# RF_Transceiver_Sch.net
KiCad netlist of a schematic drawn in Altium Designer
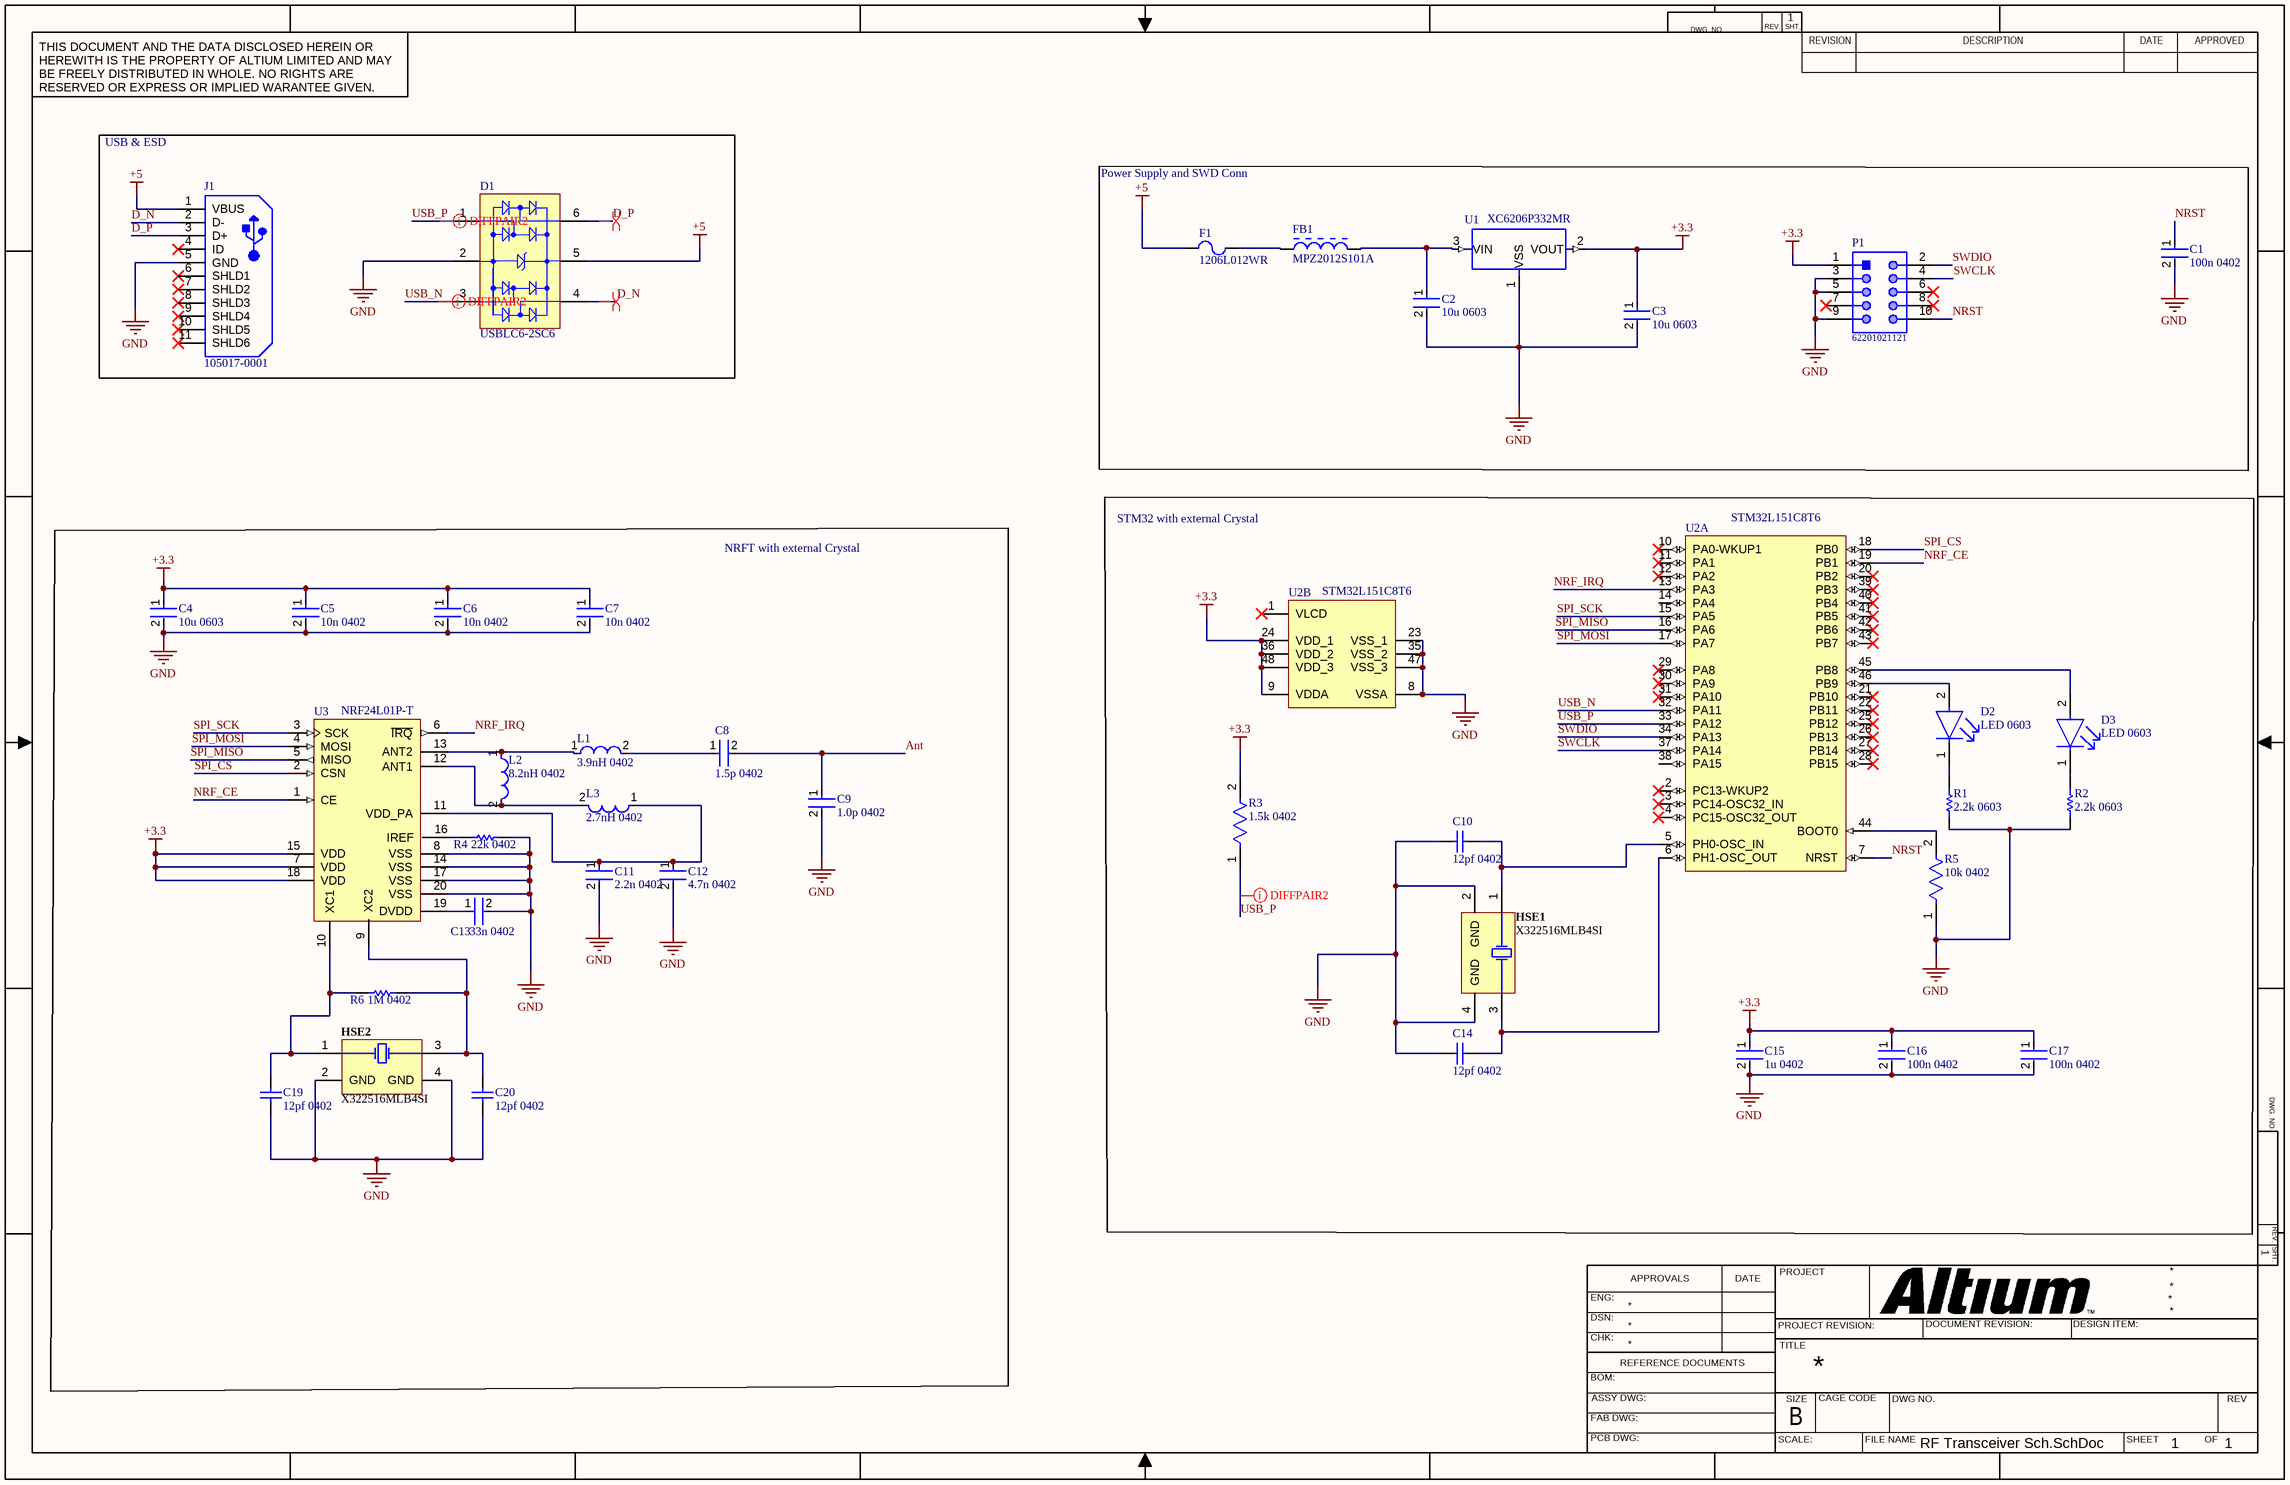
[diagram p0: RF Transceiver Sch.SchDoc]

(export (version "E")
  (design (tool "Eeschema 10.0.6"))
  (components
    (comp (ref "C1")
      (value "100n 0402")
      (footprint "FP-C0402-BB-MFG")
      (description "CAP CER 0.1UF 10V X5R 0402")
      (fields (field (name "MANUFACTURER") "Kemet") (field (name "TOLERANCE") "0.1"))
      (libsource (lib "Altium Content Vault") (part "b4654b650e69147ec39a6b967a45e02"))
    )
    (comp (ref "C2")
      (value "10u 0603")
      (footprint "FP-GRM188-0_1-e0_2_0_55-IPC_A")
      (description "Chip Multilayer Ceramic Capacitors for General Purpose, 0603, 10uF, X5R, 15%, 20%, 6.3V")
      (fields (field (name "VOLTAGE") "6.3V") (field (name "TOLERANCE") "20%"))
      (libsource (lib "Altium Content Vault") (part "02cd4be3c70576c341d710602a673aa"))
    )
    (comp (ref "C3")
      (value "10u 0603")
      (footprint "FP-GRM188-0_1-e0_2_0_55-IPC_A")
      (description "Chip Multilayer Ceramic Capacitors for General Purpose, 0603, 10uF, X5R, 15%, 20%, 6.3V")
      (fields (field (name "VOLTAGE") "6.3V") (field (name "TOLERANCE") "20%"))
      (libsource (lib "Altium Content Vault") (part "02cd4be3c70576c341d710602a673aa"))
    )
    (comp (ref "C4")
      (value "10u 0603")
      (footprint "FP-GRM188-0_1-e0_2_0_55-IPC_A")
      (description "Chip Multilayer Ceramic Capacitors for General Purpose, 0603, 10uF, X5R, 15%, 20%, 6.3V")
      (fields (field (name "VOLTAGE") "6.3V") (field (name "TOLERANCE") "20%"))
      (libsource (lib "Altium Content Vault") (part "02cd4be3c70576c341d710602a673aa"))
    )
    (comp (ref "C5")
      (value "10n 0402")
      (footprint "FP-C0402-BB-MFG")
      (description "CAP CER 0.1UF 10V X5R 0402")
      (fields (field (name "MANUFACTURER") "Kemet") (field (name "TOLERANCE") "0.1"))
      (libsource (lib "Altium Content Vault") (part "b4654b650e69147ec39a6b967a45e02"))
    )
    (comp (ref "C6")
      (value "10n 0402")
      (footprint "FP-C0402-BB-MFG")
      (description "CAP CER 0.1UF 10V X5R 0402")
      (fields (field (name "MANUFACTURER") "Kemet") (field (name "TOLERANCE") "0.1"))
      (libsource (lib "Altium Content Vault") (part "b4654b650e69147ec39a6b967a45e02"))
    )
    (comp (ref "C7")
      (value "10n 0402")
      (footprint "FP-C0402-BB-MFG")
      (description "CAP CER 0.1UF 10V X5R 0402")
      (fields (field (name "MANUFACTURER") "Kemet") (field (name "TOLERANCE") "0.1"))
      (libsource (lib "Altium Content Vault") (part "b4654b650e69147ec39a6b967a45e02"))
    )
    (comp (ref "C8")
      (value "1.5p 0402")
      (footprint "FP-C0402-BB-MFG")
      (description "CAP CER 0.1UF 10V X5R 0402")
      (fields (field (name "MANUFACTURER") "Kemet") (field (name "TOLERANCE") "0.1"))
      (libsource (lib "Altium Content Vault") (part "b4654b650e69147ec39a6b967a45e02"))
    )
    (comp (ref "C9")
      (value "1.0p 0402")
      (footprint "FP-C0402-BB-MFG")
      (description "CAP CER 0.1UF 10V X5R 0402")
      (fields (field (name "MANUFACTURER") "Kemet") (field (name "TOLERANCE") "0.1"))
      (libsource (lib "Altium Content Vault") (part "b4654b650e69147ec39a6b967a45e02"))
    )
    (comp (ref "C10")
      (value "12pf 0402")
      (footprint "CAPC1005X55X25ML05T10")
      (fields (field (name "PART NUMBER") "GRM1555C1H120GA01D") (field (name "MANUFACTURER") "Murata"))
      (libsource (lib "Altium Content Vault") (part "CAP"))
    )
    (comp (ref "C11")
      (value "2.2n 0402")
      (footprint "FP-C0402-BB-MFG")
      (description "CAP CER 0.1UF 10V X5R 0402")
      (fields (field (name "MANUFACTURER") "Kemet") (field (name "TOLERANCE") "0.1"))
      (libsource (lib "Altium Content Vault") (part "b4654b650e69147ec39a6b967a45e02"))
    )
    (comp (ref "C12")
      (value "4.7n 0402")
      (footprint "FP-C0402-BB-MFG")
      (description "CAP CER 0.1UF 10V X5R 0402")
      (fields (field (name "MANUFACTURER") "Kemet") (field (name "TOLERANCE") "0.1"))
      (libsource (lib "Altium Content Vault") (part "b4654b650e69147ec39a6b967a45e02"))
    )
    (comp (ref "C13")
      (value "33n 0402")
      (footprint "FP-C0402-BB-MFG")
      (description "CAP CER 0.1UF 10V X5R 0402")
      (fields (field (name "MANUFACTURER") "Kemet") (field (name "TOLERANCE") "0.1"))
      (libsource (lib "Altium Content Vault") (part "b4654b650e69147ec39a6b967a45e02"))
    )
    (comp (ref "C14")
      (value "12pf 0402")
      (footprint "CAPC1005X55X25ML05T10")
      (fields (field (name "PART NUMBER") "GRM1555C1H120GA01D") (field (name "MANUFACTURER") "Murata"))
      (libsource (lib "Altium Content Vault") (part "CAP"))
    )
    (comp (ref "C15")
      (value "1u 0402")
      (footprint "FP-GRM15-0_1-MFG")
      (description "CAP CER 1UF 10V X5R 0402")
      (fields
        (field (name "OCTOPART") "https://octopart.com/grm155r61a105ke15d-murata-197442")
        (field (name "MANUFACTURER PART NUMBER") "GRM155R61A105KE15D")
      )
      (libsource (lib "Altium Content Vault") (part "02cd4be3c70576c341d710602a673aa"))
    )
    (comp (ref "C16")
      (value "100n 0402")
      (footprint "FP-C0402-BB-MFG")
      (description "CAP CER 0.1UF 10V X5R 0402")
      (fields (field (name "MANUFACTURER") "Kemet") (field (name "TOLERANCE") "0.1"))
      (libsource (lib "Altium Content Vault") (part "b4654b650e69147ec39a6b967a45e02"))
    )
    (comp (ref "C17")
      (value "100n 0402")
      (footprint "FP-C0402-BB-MFG")
      (description "CAP CER 0.1UF 10V X5R 0402")
      (fields (field (name "MANUFACTURER") "Kemet") (field (name "TOLERANCE") "0.1"))
      (libsource (lib "Altium Content Vault") (part "b4654b650e69147ec39a6b967a45e02"))
    )
    (comp (ref "C19")
      (value "12pf 0402")
      (footprint "CAPC1005X55X25ML05T10")
      (fields (field (name "PART NUMBER") "GRM1555C1H120GA01D") (field (name "MANUFACTURER") "Murata"))
      (libsource (lib "Altium Content Vault") (part "CAP"))
    )
    (comp (ref "C20")
      (value "12pf 0402")
      (footprint "CAPC1005X55X25ML05T10")
      (fields (field (name "PART NUMBER") "GRM1555C1H120GA01D") (field (name "MANUFACTURER") "Murata"))
      (libsource (lib "Altium Content Vault") (part "CAP"))
    )
    (comp (ref "D1")
      (value "USBLC6-2SC6")
      (footprint "STM-SOT23-6L_V")
      (description "Very low capacitance ESD protection, 3.5 pF, -40 to 125 degC, 6-Pin SOT23, RoHS, Tape and Reel")
      (fields (field (name "MANUFACTURER") "STMicroelectronics"))
      (libsource (lib "Altium Content Vault") (part "STM-USB_DVI_HDMIULC6-4SC6X-SOT23-6L"))
    )
    (comp (ref "D2")
      (value "LED 0603")
      (footprint "FP-LTST-C191TBKT-MFG")
      (description "LED BLUE CLEAR CHIP SMD")
      (libsource (lib "Altium Content Vault") (part "8706943c75ba83719d021d2fdc84c58"))
    )
    (comp (ref "D3")
      (value "LED 0603")
      (footprint "FP-LTST-C191TBKT-MFG")
      (description "LED BLUE CLEAR CHIP SMD")
      (libsource (lib "Altium Content Vault") (part "8706943c75ba83719d021d2fdc84c58"))
    )
    (comp (ref "F1")
      (value "1206L012WR")
      (footprint "LFUS-1206L012WR_V")
      (description "POLY-FUSE(R) Resettable PTC, 30 V, -40 to 85 degC, 2-Pin SMD, RoHS, Tape and Reel")
      (fields (field (name "MANUFACTURER") "Littelfuse"))
      (libsource (lib "Altium Content Vault") (part "FUSE-2"))
    )
    (comp (ref "FB1")
      (value "MPZ2012S101A")
      (footprint "TDK-MPZ2012S101A-2_V")
      (fields (field (name "TOLERANCE") "25%") (field (name "MANUFACTURER") "TDK"))
      (libsource (lib "Altium Content Vault") (part "BEAD-2"))
    )
    (comp (ref "HSE1")
      (value "X322516MLB4SI")
      (footprint "EPSON-TSX-3225_V")
      (description "Crystal, 16 MHz, -40 to 85 degC, 4-Pin SMD, RoHS, Tape and Reel")
      (fields (field (name "MANUFACTURER") "Epson") (field (name "TOLERANCE") "10PPM"))
      (libsource (lib "") (part "XTAL-1-3-4_1"))
    )
    (comp (ref "HSE2")
      (value "X322516MLB4SI")
      (footprint "EPSON-TSX-3225_V")
      (description "Crystal, 16 MHz, -40 to 85 degC, 4-Pin SMD, RoHS, Tape and Reel")
      (fields (field (name "MANUFACTURER") "Epson") (field (name "TOLERANCE") "10PPM"))
      (libsource (lib "Altium Content Vault") (part "XTAL-1-3-4"))
    )
    (comp (ref "J1")
      (value "105017-0001")
      (footprint "USB-MICRO-B_V")
      (fields (field (name "MANUFACTURER") "Molex"))
      (libsource (lib "Altium Content Vault") (part "USB-5-6SHLD"))
    )
    (comp (ref "L1")
      (value "3.9nH 0402")
      (footprint "FP-LQW15AN_80-MFG")
      (description "Wire Wound RF Inductor for Automotive 3.4nH ±0.5nH 1950mA 0.03Ω 0402 (1005)")
      (libsource (lib "Altium Content Vault") (part "725321dda6339637d4d059423bc1c3c"))
    )
    (comp (ref "L2")
      (value "8.2nH 0402")
      (footprint "FP-LQW15AN_80-MFG")
      (description "Wire Wound RF Inductor for Automotive 3.4nH ±0.5nH 1950mA 0.03Ω 0402 (1005)")
      (libsource (lib "Altium Content Vault") (part "725321dda6339637d4d059423bc1c3c"))
    )
    (comp (ref "L3")
      (value "2.7nH 0402")
      (footprint "FP-LQW15AN_80-MFG")
      (description "Wire Wound RF Inductor for Automotive 3.4nH ±0.5nH 1950mA 0.03Ω 0402 (1005)")
      (libsource (lib "Altium Content Vault") (part "725321dda6339637d4d059423bc1c3c"))
    )
    (comp (ref "P1")
      (value "62201021121")
      (footprint "62201021121")
      (description "THT Vertical Pin Header WR-PHD, Pitch 1.27 mm, Dual Row, 10 pins")
      (fields (field (name "MANUFACTURER") "Wurth Elektronik") (field (name "PUBLISHER") "WurthElektronik"))
      (libsource (lib "Altium Content Vault") (part "WE-CN-2P-M-R10"))
    )
    (comp (ref "R1")
      (value "2.2k 0603")
      (footprint "RESC1609X50X30NL10T20")
      (fields (field (name "PART NUMBER") "CRCW06032K20FKEA") (field (name "MANUFACTURER") "Vishay Dale"))
      (libsource (lib "Altium Content Vault") (part "RES"))
    )
    (comp (ref "R2")
      (value "2.2k 0603")
      (footprint "RESC1609X50X30NL10T20")
      (fields (field (name "PART NUMBER") "CRCW06032K20FKEA") (field (name "MANUFACTURER") "Vishay Dale"))
      (libsource (lib "Altium Content Vault") (part "RES"))
    )
    (comp (ref "R3")
      (value "1.5k 0402")
      (footprint "FP-CRCW0402-e3-IPC_B")
      (description "RES SMD 10K OHM 1% 1/16W 0402")
      (fields (field (name "TOLERANCE") "1%"))
      (libsource (lib "Altium Content Vault") (part "1029c3af85768c4190bb7ad29bc67b5"))
    )
    (comp (ref "R4")
      (value "22k 0402")
      (footprint "RESC1005X40X25NL05T05")
      (fields (field (name "PART NUMBER") "CRCW040222K0FKED") (field (name "MANUFACTURER") "Vishay Dale"))
      (libsource (lib "Altium Content Vault") (part "RES"))
    )
    (comp (ref "R5")
      (value "10k 0402")
      (footprint "FP-CRCW0402-e3-IPC_B")
      (description "RES SMD 10K OHM 1% 1/16W 0402")
      (fields (field (name "TOLERANCE") "1%"))
      (libsource (lib "Altium Content Vault") (part "1029c3af85768c4190bb7ad29bc67b5"))
    )
    (comp (ref "R6")
      (value "1M 0402")
      (footprint "RESC1005X40X25NL05T05")
      (fields (field (name "PART NUMBER") "CRCW040222K0FKED") (field (name "MANUFACTURER") "Vishay Dale"))
      (libsource (lib "Altium Content Vault") (part "RES"))
    )
    (comp (ref "U1")
      (value "XC6206P332MR")
      (footprint "SOT-23")
      (description "Linear Voltage Regulator IC 1 Output 200mA SOT-23")
      (fields (field (name "MF") "Torex") (field (name "MP") "XC6206P332MR-G"))
      (libsource (lib "PMIC-LDO-XC6206P332MR-G_SOT23_") (part "PMIC-LDO-XC6206P332MR-G(SOT23)"))
    )
    (comp (ref "U2")
      (value "STM32L151C8T6")
      (footprint "STM-LQFP48_L")
      (libsource (lib "Altium Content Vault") (part "MC-ARM-STM32L15XX6_8_B-SQ48"))
    )
    (comp (ref "U3")
      (value "NRF24L01P-T")
      (footprint "NRSC-QFN-20_L")
      (description "Single Chip Transceiver, 2.4 GHz, 60 mW, 1.9 to 3.6 V, -40 to 85 degC, 20-Pin QFN, RoHS, Tray")
      (fields (field (name "MANUFACTURER") "Nordic Semiconductor"))
      (libsource (lib "Altium Content Vault") (part "NRSC-NRF24L01P-QFN-20"))
    )
  )
  (nets
    (net (code "1") (name "+3.3") (class "Default")
      (node (ref "C15") (pin "1") (pinfunction "1_1") (pintype "passive"))
      (node (ref "C16") (pin "1") (pinfunction "1_1") (pintype "passive"))
      (node (ref "C17") (pin "1") (pinfunction "1_1") (pintype "passive"))
      (node (ref "C3") (pin "1") (pinfunction "1_1") (pintype "passive"))
      (node (ref "C4") (pin "1") (pinfunction "1_1") (pintype "passive"))
      (node (ref "C5") (pin "1") (pinfunction "1_1") (pintype "passive"))
      (node (ref "C6") (pin "1") (pinfunction "1_1") (pintype "passive"))
      (node (ref "C7") (pin "1") (pinfunction "1_1") (pintype "passive"))
      (node (ref "P1") (pin "1") (pinfunction "1_1") (pintype "passive"))
      (node (ref "R3") (pin "2") (pinfunction "2_2") (pintype "passive"))
      (node (ref "U1") (pin "2") (pinfunction "VOUT_2") (pintype "output"))
      (node (ref "U2") (pin "24") (pinfunction "VDD_1_24") (pintype "power_in"))
      (node (ref "U2") (pin "36") (pinfunction "VDD_2_36") (pintype "power_in"))
      (node (ref "U2") (pin "48") (pinfunction "VDD_3_48") (pintype "power_in"))
      (node (ref "U2") (pin "9") (pinfunction "VDDA_9") (pintype "power_in"))
      (node (ref "U3") (pin "15") (pinfunction "VDD_15") (pintype "power_in"))
      (node (ref "U3") (pin "18") (pinfunction "VDD_18") (pintype "power_in"))
      (node (ref "U3") (pin "7") (pinfunction "VDD_7") (pintype "power_in"))
    )
    (net (code "2") (name "+5") (class "Default")
      (node (ref "D1") (pin "5") (pinfunction "VBUS_5") (pintype "passive"))
      (node (ref "F1") (pin "1") (pinfunction "1_1") (pintype "passive"))
      (node (ref "J1") (pin "1") (pinfunction "VBUS_1") (pintype "passive"))
    )
    (net (code "3") (name "/Ant") (class "Default")
      (node (ref "C8") (pin "2") (pinfunction "2_2") (pintype "passive"))
      (node (ref "C9") (pin "1") (pinfunction "1_1") (pintype "passive"))
    )
    (net (code "4") (name "/D_N") (class "Default")
      (node (ref "D1") (pin "4") (pinfunction "I/O_3_4") (pintype "passive"))
      (node (ref "J1") (pin "2") (pinfunction "D-_2") (pintype "passive"))
    )
    (net (code "5") (name "/D_P") (class "Default")
      (node (ref "D1") (pin "6") (pinfunction "I/O_4_6") (pintype "passive"))
      (node (ref "J1") (pin "3") (pinfunction "D+_3") (pintype "passive"))
    )
    (net (code "6") (name "/NRF_CE") (class "Default")
      (node (ref "U2") (pin "19") (pinfunction "PB1_19") (pintype "bidirectional"))
      (node (ref "U3") (pin "1") (pinfunction "CE_1") (pintype "input"))
    )
    (net (code "7") (name "/NRF_IRQ") (class "Default")
      (node (ref "U2") (pin "13") (pinfunction "PA3_13") (pintype "bidirectional"))
      (node (ref "U3") (pin "6") (pinfunction "~{IRQ}_6") (pintype "output"))
    )
    (net (code "8") (name "/NRST") (class "Default")
      (node (ref "C1") (pin "1") (pinfunction "1_1") (pintype "passive"))
      (node (ref "P1") (pin "10") (pinfunction "10_10") (pintype "passive"))
      (node (ref "U2") (pin "7") (pinfunction "NRST_7") (pintype "bidirectional"))
    )
    (net (code "9") (name "/SPI_CS") (class "Default")
      (node (ref "U2") (pin "18") (pinfunction "PB0_18") (pintype "bidirectional"))
      (node (ref "U3") (pin "2") (pinfunction "CSN_2") (pintype "input"))
    )
    (net (code "10") (name "/SPI_MISO") (class "Default")
      (node (ref "U2") (pin "16") (pinfunction "PA6_16") (pintype "bidirectional"))
      (node (ref "U3") (pin "5") (pinfunction "MISO_5") (pintype "output"))
    )
    (net (code "11") (name "/SPI_MOSI") (class "Default")
      (node (ref "U2") (pin "17") (pinfunction "PA7_17") (pintype "bidirectional"))
      (node (ref "U3") (pin "4") (pinfunction "MOSI_4") (pintype "input"))
    )
    (net (code "12") (name "/SPI_SCK") (class "Default")
      (node (ref "U2") (pin "15") (pinfunction "PA5_15") (pintype "bidirectional"))
      (node (ref "U3") (pin "3") (pinfunction "SCK_3") (pintype "input"))
    )
    (net (code "13") (name "/SWCLK") (class "Default")
      (node (ref "P1") (pin "4") (pinfunction "4_4") (pintype "passive"))
      (node (ref "U2") (pin "37") (pinfunction "PA14_37") (pintype "bidirectional"))
    )
    (net (code "14") (name "/SWDIO") (class "Default")
      (node (ref "P1") (pin "2") (pinfunction "2_2") (pintype "passive"))
      (node (ref "U2") (pin "34") (pinfunction "PA13_34") (pintype "bidirectional"))
    )
    (net (code "15") (name "/USB_N") (class "Default")
      (node (ref "D1") (pin "3") (pinfunction "I/O_2_3") (pintype "passive"))
      (node (ref "U2") (pin "32") (pinfunction "PA11_32") (pintype "bidirectional"))
    )
    (net (code "16") (name "/USB_P") (class "Default")
      (node (ref "D1") (pin "1") (pinfunction "I/O_1_1") (pintype "passive"))
      (node (ref "R3") (pin "1") (pinfunction "1_1") (pintype "passive"))
      (node (ref "U2") (pin "33") (pinfunction "PA12_33") (pintype "bidirectional"))
    )
    (net (code "17") (name "GND") (class "Default")
      (node (ref "C1") (pin "2") (pinfunction "2_2") (pintype "passive"))
      (node (ref "C10") (pin "1") (pinfunction "1_1") (pintype "passive"))
      (node (ref "C11") (pin "2") (pinfunction "2_2") (pintype "passive"))
      (node (ref "C12") (pin "2") (pinfunction "2_2") (pintype "passive"))
      (node (ref "C13") (pin "2") (pinfunction "2_2") (pintype "passive"))
      (node (ref "C14") (pin "1") (pinfunction "1_1") (pintype "passive"))
      (node (ref "C15") (pin "2") (pinfunction "2_2") (pintype "passive"))
      (node (ref "C16") (pin "2") (pinfunction "2_2") (pintype "passive"))
      (node (ref "C17") (pin "2") (pinfunction "2_2") (pintype "passive"))
      (node (ref "C19") (pin "1") (pinfunction "1_1") (pintype "passive"))
      (node (ref "C2") (pin "2") (pinfunction "2_2") (pintype "passive"))
      (node (ref "C20") (pin "1") (pinfunction "1_1") (pintype "passive"))
      (node (ref "C3") (pin "2") (pinfunction "2_2") (pintype "passive"))
      (node (ref "C4") (pin "2") (pinfunction "2_2") (pintype "passive"))
      (node (ref "C5") (pin "2") (pinfunction "2_2") (pintype "passive"))
      (node (ref "C6") (pin "2") (pinfunction "2_2") (pintype "passive"))
      (node (ref "C7") (pin "2") (pinfunction "2_2") (pintype "passive"))
      (node (ref "C9") (pin "2") (pinfunction "2_2") (pintype "passive"))
      (node (ref "D1") (pin "2") (pinfunction "GND_2") (pintype "passive"))
      (node (ref "HSE1") (pin "2") (pinfunction "GND_2") (pintype "power_in"))
      (node (ref "HSE1") (pin "4") (pinfunction "GND_4") (pintype "power_in"))
      (node (ref "HSE2") (pin "2") (pinfunction "GND_2") (pintype "power_in"))
      (node (ref "HSE2") (pin "4") (pinfunction "GND_4") (pintype "power_in"))
      (node (ref "J1") (pin "5") (pinfunction "GND_5") (pintype "passive"))
      (node (ref "P1") (pin "3") (pinfunction "3_3") (pintype "passive"))
      (node (ref "P1") (pin "5") (pinfunction "5_5") (pintype "passive"))
      (node (ref "P1") (pin "9") (pinfunction "9_9") (pintype "passive"))
      (node (ref "R1") (pin "2") (pinfunction "2_2") (pintype "passive"))
      (node (ref "R2") (pin "2") (pinfunction "2_2") (pintype "passive"))
      (node (ref "R4") (pin "2") (pinfunction "2_2") (pintype "passive"))
      (node (ref "R5") (pin "1") (pinfunction "1_1") (pintype "passive"))
      (node (ref "U1") (pin "1") (pinfunction "VSS_1") (pintype "power_in"))
      (node (ref "U2") (pin "23") (pinfunction "VSS_1_23") (pintype "power_in"))
      (node (ref "U2") (pin "35") (pinfunction "VSS_2_35") (pintype "power_in"))
      (node (ref "U2") (pin "47") (pinfunction "VSS_3_47") (pintype "power_in"))
      (node (ref "U2") (pin "8") (pinfunction "VSSA_8") (pintype "power_in"))
      (node (ref "U3") (pin "14") (pinfunction "VSS_14") (pintype "power_in"))
      (node (ref "U3") (pin "17") (pinfunction "VSS_17") (pintype "power_in"))
      (node (ref "U3") (pin "20") (pinfunction "VSS_20") (pintype "power_in"))
      (node (ref "U3") (pin "8") (pinfunction "VSS_8") (pintype "power_in"))
    )
    (net (code "18") (name "Net-(C8-Pad1)") (class "Default")
      (node (ref "C8") (pin "1") (pinfunction "1_1") (pintype "passive"))
      (node (ref "L1") (pin "2") (pinfunction "2_2") (pintype "passive"))
    )
    (net (code "19") (name "Net-(D2-A)") (class "Default")
      (node (ref "D2") (pin "2") (pinfunction "A_2") (pintype "passive"))
      (node (ref "U2") (pin "46") (pinfunction "PB9_46") (pintype "bidirectional"))
    )
    (net (code "20") (name "Net-(D2-C)") (class "Default")
      (node (ref "D2") (pin "1") (pinfunction "C_1") (pintype "passive"))
      (node (ref "R1") (pin "1") (pinfunction "1_1") (pintype "passive"))
    )
    (net (code "21") (name "Net-(D3-A)") (class "Default")
      (node (ref "D3") (pin "2") (pinfunction "A_2") (pintype "passive"))
      (node (ref "U2") (pin "45") (pinfunction "PB8_45") (pintype "bidirectional"))
    )
    (net (code "22") (name "Net-(D3-C)") (class "Default")
      (node (ref "D3") (pin "1") (pinfunction "C_1") (pintype "passive"))
      (node (ref "R2") (pin "1") (pinfunction "1_1") (pintype "passive"))
    )
    (net (code "23") (name "Net-(F1-Pad2)") (class "Default")
      (node (ref "F1") (pin "2") (pinfunction "2_2") (pintype "passive"))
      (node (ref "FB1") (pin "1") (pinfunction "1_1") (pintype "passive"))
    )
    (net (code "24") (name "Net-(HSE1-X1)") (class "Default")
      (node (ref "C10") (pin "2") (pinfunction "2_2") (pintype "passive"))
      (node (ref "HSE1") (pin "1") (pinfunction "X1_1") (pintype "passive"))
      (node (ref "U2") (pin "5") (pinfunction "PH0-OSC_IN_5") (pintype "bidirectional"))
    )
    (net (code "25") (name "Net-(HSE1-X2)") (class "Default")
      (node (ref "C14") (pin "2") (pinfunction "2_2") (pintype "passive"))
      (node (ref "HSE1") (pin "3") (pinfunction "X2_3") (pintype "passive"))
      (node (ref "U2") (pin "6") (pinfunction "PH1-OSC_OUT_6") (pintype "bidirectional"))
    )
    (net (code "26") (name "Net-(HSE2-X1)") (class "Default")
      (node (ref "C19") (pin "2") (pinfunction "2_2") (pintype "passive"))
      (node (ref "HSE2") (pin "1") (pinfunction "X1_1") (pintype "passive"))
      (node (ref "R6") (pin "1") (pinfunction "1_1") (pintype "passive"))
      (node (ref "U3") (pin "10") (pinfunction "XC1_10") (pintype "passive"))
    )
    (net (code "27") (name "Net-(HSE2-X2)") (class "Default")
      (node (ref "C20") (pin "2") (pinfunction "2_2") (pintype "passive"))
      (node (ref "HSE2") (pin "3") (pinfunction "X2_3") (pintype "passive"))
      (node (ref "R6") (pin "2") (pinfunction "2_2") (pintype "passive"))
      (node (ref "U3") (pin "9") (pinfunction "XC2_9") (pintype "passive"))
    )
    (net (code "28") (name "Net-(U1-VIN)") (class "Default")
      (node (ref "C2") (pin "1") (pinfunction "1_1") (pintype "passive"))
      (node (ref "FB1") (pin "2") (pinfunction "2_2") (pintype "passive"))
      (node (ref "U1") (pin "3") (pinfunction "VIN_3") (pintype "input"))
    )
    (net (code "29") (name "Net-(U2A-BOOT0)") (class "Default")
      (node (ref "R5") (pin "2") (pinfunction "2_2") (pintype "passive"))
      (node (ref "U2") (pin "44") (pinfunction "BOOT0_44") (pintype "input"))
    )
    (net (code "30") (name "Net-(U3-ANT1)") (class "Default")
      (node (ref "L2") (pin "2") (pinfunction "2_2") (pintype "passive"))
      (node (ref "L3") (pin "2") (pinfunction "2_2") (pintype "passive"))
      (node (ref "U3") (pin "12") (pinfunction "ANT1_12") (pintype "passive"))
    )
    (net (code "31") (name "Net-(U3-ANT2)") (class "Default")
      (node (ref "L1") (pin "1") (pinfunction "1_1") (pintype "passive"))
      (node (ref "L2") (pin "1") (pinfunction "1_1") (pintype "passive"))
      (node (ref "U3") (pin "13") (pinfunction "ANT2_13") (pintype "passive"))
    )
    (net (code "32") (name "Net-(U3-DVDD)") (class "Default")
      (node (ref "C13") (pin "1") (pinfunction "1_1") (pintype "passive"))
      (node (ref "U3") (pin "19") (pinfunction "DVDD_19") (pintype "power_in"))
    )
    (net (code "33") (name "Net-(U3-IREF)") (class "Default")
      (node (ref "R4") (pin "1") (pinfunction "1_1") (pintype "passive"))
      (node (ref "U3") (pin "16") (pinfunction "IREF_16") (pintype "passive"))
    )
    (net (code "34") (name "Net-(U3-VDD_PA)") (class "Default")
      (node (ref "C11") (pin "1") (pinfunction "1_1") (pintype "passive"))
      (node (ref "C12") (pin "1") (pinfunction "1_1") (pintype "passive"))
      (node (ref "L3") (pin "1") (pinfunction "1_1") (pintype "passive"))
      (node (ref "U3") (pin "11") (pinfunction "VDD_PA_11") (pintype "power_in"))
    )
    (net (code "35") (name "unconnected-(J1-ID-Pad4)") (class "Default")
      (node (ref "J1") (pin "4") (pinfunction "ID_4") (pintype "passive+no_connect"))
    )
    (net (code "36") (name "unconnected-(J1-SHLD1-Pad6)") (class "Default")
      (node (ref "J1") (pin "6") (pinfunction "SHLD1_6") (pintype "passive+no_connect"))
    )
    (net (code "37") (name "unconnected-(J1-SHLD2-Pad7)") (class "Default")
      (node (ref "J1") (pin "7") (pinfunction "SHLD2_7") (pintype "passive+no_connect"))
    )
    (net (code "38") (name "unconnected-(J1-SHLD3-Pad8)") (class "Default")
      (node (ref "J1") (pin "8") (pinfunction "SHLD3_8") (pintype "passive+no_connect"))
    )
    (net (code "39") (name "unconnected-(J1-SHLD4-Pad9)") (class "Default")
      (node (ref "J1") (pin "9") (pinfunction "SHLD4_9") (pintype "passive+no_connect"))
    )
    (net (code "40") (name "unconnected-(J1-SHLD5-Pad10)") (class "Default")
      (node (ref "J1") (pin "10") (pinfunction "SHLD5_10") (pintype "passive+no_connect"))
    )
    (net (code "41") (name "unconnected-(J1-SHLD6-Pad11)") (class "Default")
      (node (ref "J1") (pin "11") (pinfunction "SHLD6_11") (pintype "passive+no_connect"))
    )
    (net (code "42") (name "unconnected-(P1-Pad6)") (class "Default")
      (node (ref "P1") (pin "6") (pinfunction "6_6") (pintype "passive+no_connect"))
    )
    (net (code "43") (name "unconnected-(P1-Pad7)") (class "Default")
      (node (ref "P1") (pin "7") (pinfunction "7_7") (pintype "passive+no_connect"))
    )
    (net (code "44") (name "unconnected-(P1-Pad8)") (class "Default")
      (node (ref "P1") (pin "8") (pinfunction "8_8") (pintype "passive+no_connect"))
    )
    (net (code "45") (name "unconnected-(U2A-PA0-WKUP1-Pad10)") (class "Default")
      (node (ref "U2") (pin "10") (pinfunction "PA0-WKUP1_10") (pintype "bidirectional+no_connect"))
    )
    (net (code "46") (name "unconnected-(U2A-PA1-Pad11)") (class "Default")
      (node (ref "U2") (pin "11") (pinfunction "PA1_11") (pintype "bidirectional+no_connect"))
    )
    (net (code "47") (name "unconnected-(U2A-PA2-Pad12)") (class "Default")
      (node (ref "U2") (pin "12") (pinfunction "PA2_12") (pintype "bidirectional+no_connect"))
    )
    (net (code "48") (name "unconnected-(U2A-PA4-Pad14)") (class "Default")
      (node (ref "U2") (pin "14") (pinfunction "PA4_14") (pintype "bidirectional"))
    )
    (net (code "49") (name "unconnected-(U2A-PA8-Pad29)") (class "Default")
      (node (ref "U2") (pin "29") (pinfunction "PA8_29") (pintype "bidirectional+no_connect"))
    )
    (net (code "50") (name "unconnected-(U2A-PA9-Pad30)") (class "Default")
      (node (ref "U2") (pin "30") (pinfunction "PA9_30") (pintype "bidirectional+no_connect"))
    )
    (net (code "51") (name "unconnected-(U2A-PA10-Pad31)") (class "Default")
      (node (ref "U2") (pin "31") (pinfunction "PA10_31") (pintype "bidirectional+no_connect"))
    )
    (net (code "52") (name "unconnected-(U2A-PA15-Pad38)") (class "Default")
      (node (ref "U2") (pin "38") (pinfunction "PA15_38") (pintype "bidirectional"))
    )
    (net (code "53") (name "unconnected-(U2A-PB2-Pad20)") (class "Default")
      (node (ref "U2") (pin "20") (pinfunction "PB2_20") (pintype "bidirectional+no_connect"))
    )
    (net (code "54") (name "unconnected-(U2A-PB3-Pad39)") (class "Default")
      (node (ref "U2") (pin "39") (pinfunction "PB3_39") (pintype "bidirectional+no_connect"))
    )
    (net (code "55") (name "unconnected-(U2A-PB4-Pad40)") (class "Default")
      (node (ref "U2") (pin "40") (pinfunction "PB4_40") (pintype "bidirectional+no_connect"))
    )
    (net (code "56") (name "unconnected-(U2A-PB5-Pad41)") (class "Default")
      (node (ref "U2") (pin "41") (pinfunction "PB5_41") (pintype "bidirectional+no_connect"))
    )
    (net (code "57") (name "unconnected-(U2A-PB6-Pad42)") (class "Default")
      (node (ref "U2") (pin "42") (pinfunction "PB6_42") (pintype "bidirectional+no_connect"))
    )
    (net (code "58") (name "unconnected-(U2A-PB7-Pad43)") (class "Default")
      (node (ref "U2") (pin "43") (pinfunction "PB7_43") (pintype "bidirectional+no_connect"))
    )
    (net (code "59") (name "unconnected-(U2A-PB10-Pad21)") (class "Default")
      (node (ref "U2") (pin "21") (pinfunction "PB10_21") (pintype "bidirectional+no_connect"))
    )
    (net (code "60") (name "unconnected-(U2A-PB11-Pad22)") (class "Default")
      (node (ref "U2") (pin "22") (pinfunction "PB11_22") (pintype "bidirectional+no_connect"))
    )
    (net (code "61") (name "unconnected-(U2A-PB12-Pad25)") (class "Default")
      (node (ref "U2") (pin "25") (pinfunction "PB12_25") (pintype "bidirectional+no_connect"))
    )
    (net (code "62") (name "unconnected-(U2A-PB13-Pad26)") (class "Default")
      (node (ref "U2") (pin "26") (pinfunction "PB13_26") (pintype "bidirectional+no_connect"))
    )
    (net (code "63") (name "unconnected-(U2A-PB14-Pad27)") (class "Default")
      (node (ref "U2") (pin "27") (pinfunction "PB14_27") (pintype "bidirectional+no_connect"))
    )
    (net (code "64") (name "unconnected-(U2A-PB15-Pad28)") (class "Default")
      (node (ref "U2") (pin "28") (pinfunction "PB15_28") (pintype "bidirectional+no_connect"))
    )
    (net (code "65") (name "unconnected-(U2A-PC13-WKUP2-Pad2)") (class "Default")
      (node (ref "U2") (pin "2") (pinfunction "PC13-WKUP2_2") (pintype "bidirectional+no_connect"))
    )
    (net (code "66") (name "unconnected-(U2A-PC14-OSC32_IN-Pad3)") (class "Default")
      (node (ref "U2") (pin "3") (pinfunction "PC14-OSC32_IN_3") (pintype "bidirectional+no_connect"))
    )
    (net (code "67") (name "unconnected-(U2A-PC15-OSC32_OUT-Pad4)") (class "Default")
      (node (ref "U2") (pin "4") (pinfunction "PC15-OSC32_OUT_4") (pintype "bidirectional+no_connect"))
    )
    (net (code "68") (name "unconnected-(U2B-VLCD-Pad1)") (class "Default")
      (node (ref "U2") (pin "1") (pinfunction "VLCD_1") (pintype "power_in+no_connect"))
    )
  )
)
